# Zynq_DDR_Interface_Termination.net
KiCad netlist of a schematic drawn in Altium Designer
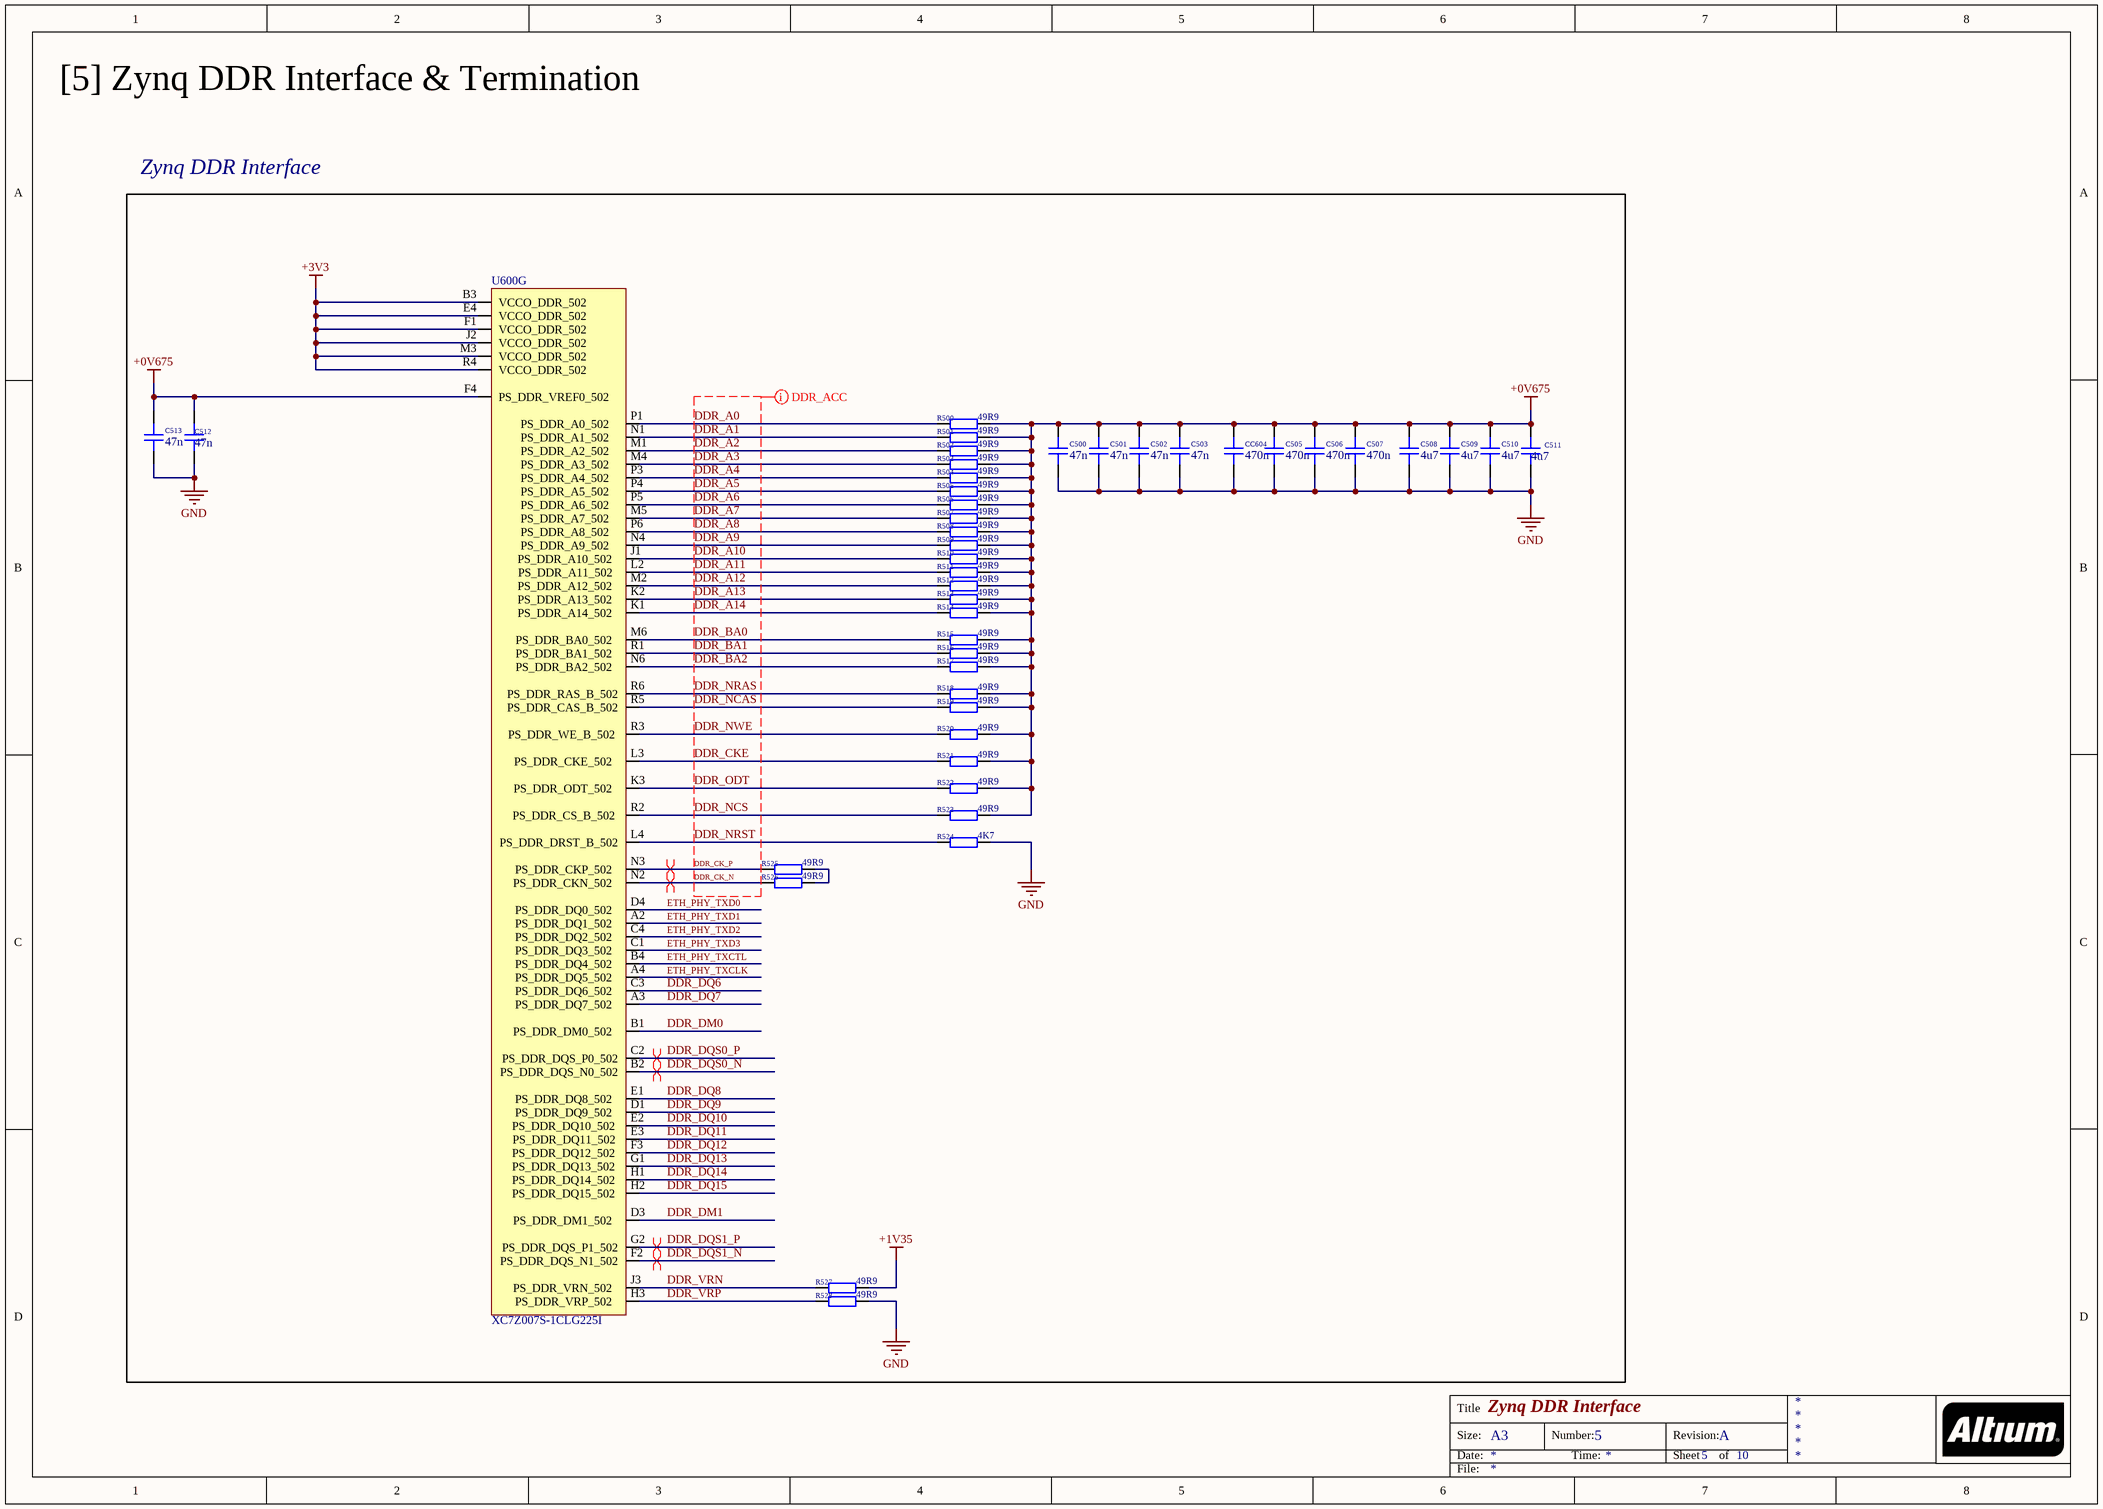
[diagram p0: Zynq DDR Interface & Termination.SchDoc]

(export (version "E")
  (design (tool "Eeschema 10.0.6"))
  (components
    (comp (ref "C500")
      (value "47n")
      (footprint "CAP_1210")
      (description "Capacitor SMD 1210")
      (libsource (lib "Schematic-Lib-PhilsLab") (part "CAP_1210"))
    )
    (comp (ref "C501")
      (value "47n")
      (footprint "CAP_1210")
      (description "Capacitor SMD 1210")
      (libsource (lib "Schematic-Lib-PhilsLab") (part "CAP_1210"))
    )
    (comp (ref "C502")
      (value "47n")
      (footprint "CAP_1210")
      (description "Capacitor SMD 1210")
      (libsource (lib "Schematic-Lib-PhilsLab") (part "CAP_1210"))
    )
    (comp (ref "C503")
      (value "47n")
      (footprint "CAP_1210")
      (description "Capacitor SMD 1210")
      (libsource (lib "Schematic-Lib-PhilsLab") (part "CAP_1210"))
    )
    (comp (ref "C505")
      (value "470n")
      (footprint "CAP_1210")
      (description "Capacitor SMD 1210")
      (libsource (lib "Schematic-Lib-PhilsLab") (part "CAP_1210"))
    )
    (comp (ref "C506")
      (value "470n")
      (footprint "CAP_1210")
      (description "Capacitor SMD 1210")
      (libsource (lib "Schematic-Lib-PhilsLab") (part "CAP_1210"))
    )
    (comp (ref "C507")
      (value "470n")
      (footprint "CAP_1210")
      (description "Capacitor SMD 1210")
      (libsource (lib "Schematic-Lib-PhilsLab") (part "CAP_1210"))
    )
    (comp (ref "C508")
      (value "4u7")
      (footprint "CAP_1210")
      (description "Capacitor SMD 1210")
      (libsource (lib "Schematic-Lib-PhilsLab") (part "CAP_1210"))
    )
    (comp (ref "C509")
      (value "4u7")
      (footprint "CAP_1210")
      (description "Capacitor SMD 1210")
      (libsource (lib "Schematic-Lib-PhilsLab") (part "CAP_1210"))
    )
    (comp (ref "C510")
      (value "4u7")
      (footprint "CAP_1210")
      (description "Capacitor SMD 1210")
      (libsource (lib "Schematic-Lib-PhilsLab") (part "CAP_1210"))
    )
    (comp (ref "C511")
      (value "4u7")
      (footprint "CAP_1210")
      (description "Capacitor SMD 1210")
      (libsource (lib "Schematic-Lib-PhilsLab") (part "CAP_1210"))
    )
    (comp (ref "C512")
      (value "47n")
      (footprint "CAP_1210")
      (description "Capacitor SMD 1210")
      (libsource (lib "Schematic-Lib-PhilsLab") (part "CAP_1210"))
    )
    (comp (ref "C513")
      (value "47n")
      (footprint "CAP_1210")
      (description "Capacitor SMD 1210")
      (libsource (lib "Schematic-Lib-PhilsLab") (part "CAP_1210"))
    )
    (comp (ref "CC604")
      (value "470n")
      (footprint "CAP_1210")
      (description "Capacitor SMD 1210")
      (libsource (lib "Schematic-Lib-PhilsLab") (part "CAP_1210"))
    )
    (comp (ref "R500")
      (value "49R9")
      (footprint "RES_0402")
      (description "Resistor SMD 0402")
      (libsource (lib "Schematic-Lib-PhilsLab") (part "RES_0402"))
    )
    (comp (ref "R501")
      (value "49R9")
      (footprint "RES_0402")
      (description "Resistor SMD 0402")
      (libsource (lib "Schematic-Lib-PhilsLab") (part "RES_0402"))
    )
    (comp (ref "R502")
      (value "49R9")
      (footprint "RES_0402")
      (description "Resistor SMD 0402")
      (libsource (lib "Schematic-Lib-PhilsLab") (part "RES_0402"))
    )
    (comp (ref "R503")
      (value "49R9")
      (footprint "RES_0402")
      (description "Resistor SMD 0402")
      (libsource (lib "Schematic-Lib-PhilsLab") (part "RES_0402"))
    )
    (comp (ref "R504")
      (value "49R9")
      (footprint "RES_0402")
      (description "Resistor SMD 0402")
      (libsource (lib "Schematic-Lib-PhilsLab") (part "RES_0402"))
    )
    (comp (ref "R505")
      (value "49R9")
      (footprint "RES_0402")
      (description "Resistor SMD 0402")
      (libsource (lib "Schematic-Lib-PhilsLab") (part "RES_0402"))
    )
    (comp (ref "R506")
      (value "49R9")
      (footprint "RES_0402")
      (description "Resistor SMD 0402")
      (libsource (lib "Schematic-Lib-PhilsLab") (part "RES_0402"))
    )
    (comp (ref "R507")
      (value "49R9")
      (footprint "RES_0402")
      (description "Resistor SMD 0402")
      (libsource (lib "Schematic-Lib-PhilsLab") (part "RES_0402"))
    )
    (comp (ref "R508")
      (value "49R9")
      (footprint "RES_0402")
      (description "Resistor SMD 0402")
      (libsource (lib "Schematic-Lib-PhilsLab") (part "RES_0402"))
    )
    (comp (ref "R509")
      (value "49R9")
      (footprint "RES_0402")
      (description "Resistor SMD 0402")
      (libsource (lib "Schematic-Lib-PhilsLab") (part "RES_0402"))
    )
    (comp (ref "R510")
      (value "49R9")
      (footprint "RES_0402")
      (description "Resistor SMD 0402")
      (libsource (lib "Schematic-Lib-PhilsLab") (part "RES_0402"))
    )
    (comp (ref "R511")
      (value "49R9")
      (footprint "RES_0402")
      (description "Resistor SMD 0402")
      (libsource (lib "Schematic-Lib-PhilsLab") (part "RES_0402"))
    )
    (comp (ref "R512")
      (value "49R9")
      (footprint "RES_0402")
      (description "Resistor SMD 0402")
      (libsource (lib "Schematic-Lib-PhilsLab") (part "RES_0402"))
    )
    (comp (ref "R513")
      (value "49R9")
      (footprint "RES_0402")
      (description "Resistor SMD 0402")
      (libsource (lib "Schematic-Lib-PhilsLab") (part "RES_0402"))
    )
    (comp (ref "R514")
      (value "49R9")
      (footprint "RES_0402")
      (description "Resistor SMD 0402")
      (libsource (lib "Schematic-Lib-PhilsLab") (part "RES_0402"))
    )
    (comp (ref "R515")
      (value "49R9")
      (footprint "RES_0402")
      (description "Resistor SMD 0402")
      (libsource (lib "Schematic-Lib-PhilsLab") (part "RES_0402"))
    )
    (comp (ref "R516")
      (value "49R9")
      (footprint "RES_0402")
      (description "Resistor SMD 0402")
      (libsource (lib "Schematic-Lib-PhilsLab") (part "RES_0402"))
    )
    (comp (ref "R517")
      (value "49R9")
      (footprint "RES_0402")
      (description "Resistor SMD 0402")
      (libsource (lib "Schematic-Lib-PhilsLab") (part "RES_0402"))
    )
    (comp (ref "R518")
      (value "49R9")
      (footprint "RES_0402")
      (description "Resistor SMD 0402")
      (libsource (lib "Schematic-Lib-PhilsLab") (part "RES_0402"))
    )
    (comp (ref "R519")
      (value "49R9")
      (footprint "RES_0402")
      (description "Resistor SMD 0402")
      (libsource (lib "Schematic-Lib-PhilsLab") (part "RES_0402"))
    )
    (comp (ref "R520")
      (value "49R9")
      (footprint "RES_0402")
      (description "Resistor SMD 0402")
      (libsource (lib "Schematic-Lib-PhilsLab") (part "RES_0402"))
    )
    (comp (ref "R521")
      (value "49R9")
      (footprint "RES_0402")
      (description "Resistor SMD 0402")
      (libsource (lib "Schematic-Lib-PhilsLab") (part "RES_0402"))
    )
    (comp (ref "R522")
      (value "49R9")
      (footprint "RES_0402")
      (description "Resistor SMD 0402")
      (libsource (lib "Schematic-Lib-PhilsLab") (part "RES_0402"))
    )
    (comp (ref "R523")
      (value "49R9")
      (footprint "RES_0402")
      (description "Resistor SMD 0402")
      (libsource (lib "Schematic-Lib-PhilsLab") (part "RES_0402"))
    )
    (comp (ref "R524")
      (value "4K7")
      (footprint "RES_0402")
      (description "Resistor SMD 0402")
      (libsource (lib "Schematic-Lib-PhilsLab") (part "RES_0402"))
    )
    (comp (ref "R525")
      (value "49R9")
      (footprint "RES_0402")
      (description "Resistor SMD 0402")
      (libsource (lib "Schematic-Lib-PhilsLab") (part "RES_0402"))
    )
    (comp (ref "R526")
      (value "49R9")
      (footprint "RES_0402")
      (description "Resistor SMD 0402")
      (libsource (lib "Schematic-Lib-PhilsLab") (part "RES_0402"))
    )
    (comp (ref "R527")
      (value "49R9")
      (footprint "RES_0402")
      (description "Resistor SMD 0402")
      (libsource (lib "Schematic-Lib-PhilsLab") (part "RES_0402"))
    )
    (comp (ref "R528")
      (value "49R9")
      (footprint "RES_0402")
      (description "Resistor SMD 0402")
      (libsource (lib "Schematic-Lib-PhilsLab") (part "RES_0402"))
    )
    (comp (ref "U600")
      (value "XC7Z007S-1CLG225I")
      (footprint "CLG225")
      (description "Xilinx FPGA SoC Zynq 7-Series XC7Z007S CLG255 Package Industrial Temperature Grade")
      (fields (field (name "MANUFACTURER") "Xilinx"))
      (libsource (lib "Schematic-Lib-PhilsLab") (part "XC7Z007S-1CLG225I"))
    )
  )
  (nets
    (net (code "1") (name "+0V675") (class "Default")
      (node (ref "C500") (pin "2") (pinfunction "2_2") (pintype "passive"))
      (node (ref "C501") (pin "2") (pinfunction "2_2") (pintype "passive"))
      (node (ref "C502") (pin "2") (pinfunction "2_2") (pintype "passive"))
      (node (ref "C503") (pin "2") (pinfunction "2_2") (pintype "passive"))
      (node (ref "C505") (pin "2") (pinfunction "2_2") (pintype "passive"))
      (node (ref "C506") (pin "2") (pinfunction "2_2") (pintype "passive"))
      (node (ref "C507") (pin "2") (pinfunction "2_2") (pintype "passive"))
      (node (ref "C508") (pin "2") (pinfunction "2_2") (pintype "passive"))
      (node (ref "C509") (pin "2") (pinfunction "2_2") (pintype "passive"))
      (node (ref "C510") (pin "2") (pinfunction "2_2") (pintype "passive"))
      (node (ref "C511") (pin "2") (pinfunction "2_2") (pintype "passive"))
      (node (ref "C512") (pin "2") (pinfunction "2_2") (pintype "passive"))
      (node (ref "C513") (pin "2") (pinfunction "2_2") (pintype "passive"))
      (node (ref "CC604") (pin "2") (pinfunction "2_2") (pintype "passive"))
      (node (ref "R500") (pin "2") (pinfunction "2_2") (pintype "passive"))
      (node (ref "R501") (pin "2") (pinfunction "2_2") (pintype "passive"))
      (node (ref "R502") (pin "2") (pinfunction "2_2") (pintype "passive"))
      (node (ref "R503") (pin "2") (pinfunction "2_2") (pintype "passive"))
      (node (ref "R504") (pin "2") (pinfunction "2_2") (pintype "passive"))
      (node (ref "R505") (pin "2") (pinfunction "2_2") (pintype "passive"))
      (node (ref "R506") (pin "2") (pinfunction "2_2") (pintype "passive"))
      (node (ref "R507") (pin "2") (pinfunction "2_2") (pintype "passive"))
      (node (ref "R508") (pin "2") (pinfunction "2_2") (pintype "passive"))
      (node (ref "R509") (pin "2") (pinfunction "2_2") (pintype "passive"))
      (node (ref "R510") (pin "2") (pinfunction "2_2") (pintype "passive"))
      (node (ref "R511") (pin "2") (pinfunction "2_2") (pintype "passive"))
      (node (ref "R512") (pin "2") (pinfunction "2_2") (pintype "passive"))
      (node (ref "R513") (pin "2") (pinfunction "2_2") (pintype "passive"))
      (node (ref "R514") (pin "2") (pinfunction "2_2") (pintype "passive"))
      (node (ref "R515") (pin "2") (pinfunction "2_2") (pintype "passive"))
      (node (ref "R516") (pin "2") (pinfunction "2_2") (pintype "passive"))
      (node (ref "R517") (pin "2") (pinfunction "2_2") (pintype "passive"))
      (node (ref "R518") (pin "2") (pinfunction "2_2") (pintype "passive"))
      (node (ref "R519") (pin "2") (pinfunction "2_2") (pintype "passive"))
      (node (ref "R520") (pin "2") (pinfunction "2_2") (pintype "passive"))
      (node (ref "R521") (pin "2") (pinfunction "2_2") (pintype "passive"))
      (node (ref "R522") (pin "2") (pinfunction "2_2") (pintype "passive"))
      (node (ref "R523") (pin "2") (pinfunction "2_2") (pintype "passive"))
      (node (ref "U600") (pin "F4") (pinfunction "PS_DDR_VREF0_502_F4") (pintype "passive"))
    )
    (net (code "2") (name "+1V35") (class "Default")
      (node (ref "R527") (pin "2") (pinfunction "2_2") (pintype "passive"))
    )
    (net (code "3") (name "+3V3") (class "Default")
      (node (ref "U600") (pin "B3") (pinfunction "VCCO_DDR_502_B3") (pintype "passive"))
      (node (ref "U600") (pin "E4") (pinfunction "VCCO_DDR_502_E4") (pintype "passive"))
      (node (ref "U600") (pin "F1") (pinfunction "VCCO_DDR_502_F1") (pintype "passive"))
      (node (ref "U600") (pin "J2") (pinfunction "VCCO_DDR_502_J2") (pintype "passive"))
      (node (ref "U600") (pin "M3") (pinfunction "VCCO_DDR_502_M3") (pintype "passive"))
      (node (ref "U600") (pin "R4") (pinfunction "VCCO_DDR_502_R4") (pintype "passive"))
    )
    (net (code "4") (name "/DDR_A0") (class "Default")
      (node (ref "R500") (pin "1") (pinfunction "1_1") (pintype "passive"))
      (node (ref "U600") (pin "P1") (pinfunction "PS_DDR_A0_502_P1") (pintype "passive"))
    )
    (net (code "5") (name "/DDR_A1") (class "Default")
      (node (ref "R501") (pin "1") (pinfunction "1_1") (pintype "passive"))
      (node (ref "U600") (pin "N1") (pinfunction "PS_DDR_A1_502_N1") (pintype "passive"))
    )
    (net (code "6") (name "/DDR_A2") (class "Default")
      (node (ref "R502") (pin "1") (pinfunction "1_1") (pintype "passive"))
      (node (ref "U600") (pin "M1") (pinfunction "PS_DDR_A2_502_M1") (pintype "passive"))
    )
    (net (code "7") (name "/DDR_A3") (class "Default")
      (node (ref "R503") (pin "1") (pinfunction "1_1") (pintype "passive"))
      (node (ref "U600") (pin "M4") (pinfunction "PS_DDR_A3_502_M4") (pintype "passive"))
    )
    (net (code "8") (name "/DDR_A4") (class "Default")
      (node (ref "R504") (pin "1") (pinfunction "1_1") (pintype "passive"))
      (node (ref "U600") (pin "P3") (pinfunction "PS_DDR_A4_502_P3") (pintype "passive"))
    )
    (net (code "9") (name "/DDR_A5") (class "Default")
      (node (ref "R505") (pin "1") (pinfunction "1_1") (pintype "passive"))
      (node (ref "U600") (pin "P4") (pinfunction "PS_DDR_A5_502_P4") (pintype "passive"))
    )
    (net (code "10") (name "/DDR_A6") (class "Default")
      (node (ref "R506") (pin "1") (pinfunction "1_1") (pintype "passive"))
      (node (ref "U600") (pin "P5") (pinfunction "PS_DDR_A6_502_P5") (pintype "passive"))
    )
    (net (code "11") (name "/DDR_A7") (class "Default")
      (node (ref "R507") (pin "1") (pinfunction "1_1") (pintype "passive"))
      (node (ref "U600") (pin "M5") (pinfunction "PS_DDR_A7_502_M5") (pintype "passive"))
    )
    (net (code "12") (name "/DDR_A8") (class "Default")
      (node (ref "R508") (pin "1") (pinfunction "1_1") (pintype "passive"))
      (node (ref "U600") (pin "P6") (pinfunction "PS_DDR_A8_502_P6") (pintype "passive"))
    )
    (net (code "13") (name "/DDR_A9") (class "Default")
      (node (ref "R509") (pin "1") (pinfunction "1_1") (pintype "passive"))
      (node (ref "U600") (pin "N4") (pinfunction "PS_DDR_A9_502_N4") (pintype "passive"))
    )
    (net (code "14") (name "/DDR_A10") (class "Default")
      (node (ref "R510") (pin "1") (pinfunction "1_1") (pintype "passive"))
      (node (ref "U600") (pin "J1") (pinfunction "PS_DDR_A10_502_J1") (pintype "passive"))
    )
    (net (code "15") (name "/DDR_A11") (class "Default")
      (node (ref "R511") (pin "1") (pinfunction "1_1") (pintype "passive"))
      (node (ref "U600") (pin "L2") (pinfunction "PS_DDR_A11_502_L2") (pintype "passive"))
    )
    (net (code "16") (name "/DDR_A12") (class "Default")
      (node (ref "R512") (pin "1") (pinfunction "1_1") (pintype "passive"))
      (node (ref "U600") (pin "M2") (pinfunction "PS_DDR_A12_502_M2") (pintype "passive"))
    )
    (net (code "17") (name "/DDR_A13") (class "Default")
      (node (ref "R513") (pin "1") (pinfunction "1_1") (pintype "passive"))
      (node (ref "U600") (pin "K2") (pinfunction "PS_DDR_A13_502_K2") (pintype "passive"))
    )
    (net (code "18") (name "/DDR_A14") (class "Default")
      (node (ref "R514") (pin "1") (pinfunction "1_1") (pintype "passive"))
      (node (ref "U600") (pin "K1") (pinfunction "PS_DDR_A14_502_K1") (pintype "passive"))
    )
    (net (code "19") (name "/DDR_BA0") (class "Default")
      (node (ref "R515") (pin "1") (pinfunction "1_1") (pintype "passive"))
      (node (ref "U600") (pin "M6") (pinfunction "PS_DDR_BA0_502_M6") (pintype "passive"))
    )
    (net (code "20") (name "/DDR_BA1") (class "Default")
      (node (ref "R516") (pin "1") (pinfunction "1_1") (pintype "passive"))
      (node (ref "U600") (pin "R1") (pinfunction "PS_DDR_BA1_502_R1") (pintype "passive"))
    )
    (net (code "21") (name "/DDR_BA2") (class "Default")
      (node (ref "R517") (pin "1") (pinfunction "1_1") (pintype "passive"))
      (node (ref "U600") (pin "N6") (pinfunction "PS_DDR_BA2_502_N6") (pintype "passive"))
    )
    (net (code "22") (name "/DDR_CKE") (class "Default")
      (node (ref "R521") (pin "1") (pinfunction "1_1") (pintype "passive"))
      (node (ref "U600") (pin "L3") (pinfunction "PS_DDR_CKE_502_L3") (pintype "passive"))
    )
    (net (code "23") (name "/DDR_CK_N") (class "Default")
      (node (ref "R526") (pin "1") (pinfunction "1_1") (pintype "passive"))
      (node (ref "U600") (pin "N2") (pinfunction "PS_DDR_CKN_502_N2") (pintype "passive"))
    )
    (net (code "24") (name "/DDR_CK_P") (class "Default")
      (node (ref "R525") (pin "1") (pinfunction "1_1") (pintype "passive"))
      (node (ref "U600") (pin "N3") (pinfunction "PS_DDR_CKP_502_N3") (pintype "passive"))
    )
    (net (code "25") (name "/DDR_DM0") (class "Default")
      (node (ref "U600") (pin "B1") (pinfunction "PS_DDR_DM0_502_B1") (pintype "passive"))
    )
    (net (code "26") (name "/DDR_DM1") (class "Default")
      (node (ref "U600") (pin "D3") (pinfunction "PS_DDR_DM1_502_D3") (pintype "passive"))
    )
    (net (code "27") (name "/DDR_DQ6") (class "Default")
      (node (ref "U600") (pin "C3") (pinfunction "PS_DDR_DQ6_502_C3") (pintype "passive"))
    )
    (net (code "28") (name "/DDR_DQ7") (class "Default")
      (node (ref "U600") (pin "A3") (pinfunction "PS_DDR_DQ7_502_A3") (pintype "passive"))
    )
    (net (code "29") (name "/DDR_DQ8") (class "Default")
      (node (ref "U600") (pin "E1") (pinfunction "PS_DDR_DQ8_502_E1") (pintype "passive"))
    )
    (net (code "30") (name "/DDR_DQ9") (class "Default")
      (node (ref "U600") (pin "D1") (pinfunction "PS_DDR_DQ9_502_D1") (pintype "passive"))
    )
    (net (code "31") (name "/DDR_DQ10") (class "Default")
      (node (ref "U600") (pin "E2") (pinfunction "PS_DDR_DQ10_502_E2") (pintype "passive"))
    )
    (net (code "32") (name "/DDR_DQ11") (class "Default")
      (node (ref "U600") (pin "E3") (pinfunction "PS_DDR_DQ11_502_E3") (pintype "passive"))
    )
    (net (code "33") (name "/DDR_DQ12") (class "Default")
      (node (ref "U600") (pin "F3") (pinfunction "PS_DDR_DQ12_502_F3") (pintype "passive"))
    )
    (net (code "34") (name "/DDR_DQ13") (class "Default")
      (node (ref "U600") (pin "G1") (pinfunction "PS_DDR_DQ13_502_G1") (pintype "passive"))
    )
    (net (code "35") (name "/DDR_DQ14") (class "Default")
      (node (ref "U600") (pin "H1") (pinfunction "PS_DDR_DQ14_502_H1") (pintype "passive"))
    )
    (net (code "36") (name "/DDR_DQ15") (class "Default")
      (node (ref "U600") (pin "H2") (pinfunction "PS_DDR_DQ15_502_H2") (pintype "passive"))
    )
    (net (code "37") (name "/DDR_DQS0_N") (class "Default")
      (node (ref "U600") (pin "B2") (pinfunction "PS_DDR_DQS_N0_502_B2") (pintype "passive"))
    )
    (net (code "38") (name "/DDR_DQS0_P") (class "Default")
      (node (ref "U600") (pin "C2") (pinfunction "PS_DDR_DQS_P0_502_C2") (pintype "passive"))
    )
    (net (code "39") (name "/DDR_DQS1_N") (class "Default")
      (node (ref "U600") (pin "F2") (pinfunction "PS_DDR_DQS_N1_502_F2") (pintype "passive"))
    )
    (net (code "40") (name "/DDR_DQS1_P") (class "Default")
      (node (ref "U600") (pin "G2") (pinfunction "PS_DDR_DQS_P1_502_G2") (pintype "passive"))
    )
    (net (code "41") (name "/DDR_NCAS") (class "Default")
      (node (ref "R519") (pin "1") (pinfunction "1_1") (pintype "passive"))
      (node (ref "U600") (pin "R5") (pinfunction "PS_DDR_CAS_B_502_R5") (pintype "passive"))
    )
    (net (code "42") (name "/DDR_NCS") (class "Default")
      (node (ref "R523") (pin "1") (pinfunction "1_1") (pintype "passive"))
      (node (ref "U600") (pin "R2") (pinfunction "PS_DDR_CS_B_502_R2") (pintype "passive"))
    )
    (net (code "43") (name "/DDR_NRAS") (class "Default")
      (node (ref "R518") (pin "1") (pinfunction "1_1") (pintype "passive"))
      (node (ref "U600") (pin "R6") (pinfunction "PS_DDR_RAS_B_502_R6") (pintype "passive"))
    )
    (net (code "44") (name "/DDR_NRST") (class "Default")
      (node (ref "R524") (pin "1") (pinfunction "1_1") (pintype "passive"))
      (node (ref "U600") (pin "L4") (pinfunction "PS_DDR_DRST_B_502_L4") (pintype "passive"))
    )
    (net (code "45") (name "/DDR_NWE") (class "Default")
      (node (ref "R520") (pin "1") (pinfunction "1_1") (pintype "passive"))
      (node (ref "U600") (pin "R3") (pinfunction "PS_DDR_WE_B_502_R3") (pintype "passive"))
    )
    (net (code "46") (name "/DDR_ODT") (class "Default")
      (node (ref "R522") (pin "1") (pinfunction "1_1") (pintype "passive"))
      (node (ref "U600") (pin "K3") (pinfunction "PS_DDR_ODT_502_K3") (pintype "passive"))
    )
    (net (code "47") (name "/DDR_VRN") (class "Default")
      (node (ref "R527") (pin "1") (pinfunction "1_1") (pintype "passive"))
      (node (ref "U600") (pin "J3") (pinfunction "PS_DDR_VRN_502_J3") (pintype "passive"))
    )
    (net (code "48") (name "/DDR_VRP") (class "Default")
      (node (ref "R528") (pin "1") (pinfunction "1_1") (pintype "passive"))
      (node (ref "U600") (pin "H3") (pinfunction "PS_DDR_VRP_502_H3") (pintype "passive"))
    )
    (net (code "49") (name "/ETH_PHY_TXCLK") (class "Default")
      (node (ref "U600") (pin "A4") (pinfunction "PS_DDR_DQ5_502_A4") (pintype "passive"))
    )
    (net (code "50") (name "/ETH_PHY_TXCTL") (class "Default")
      (node (ref "U600") (pin "B4") (pinfunction "PS_DDR_DQ4_502_B4") (pintype "passive"))
    )
    (net (code "51") (name "/ETH_PHY_TXD0") (class "Default")
      (node (ref "U600") (pin "D4") (pinfunction "PS_DDR_DQ0_502_D4") (pintype "passive"))
    )
    (net (code "52") (name "/ETH_PHY_TXD1") (class "Default")
      (node (ref "U600") (pin "A2") (pinfunction "PS_DDR_DQ1_502_A2") (pintype "passive"))
    )
    (net (code "53") (name "/ETH_PHY_TXD2") (class "Default")
      (node (ref "U600") (pin "C4") (pinfunction "PS_DDR_DQ2_502_C4") (pintype "passive"))
    )
    (net (code "54") (name "/ETH_PHY_TXD3") (class "Default")
      (node (ref "U600") (pin "C1") (pinfunction "PS_DDR_DQ3_502_C1") (pintype "passive"))
    )
    (net (code "55") (name "GND") (class "Default")
      (node (ref "C500") (pin "1") (pinfunction "1_1") (pintype "passive"))
      (node (ref "C501") (pin "1") (pinfunction "1_1") (pintype "passive"))
      (node (ref "C502") (pin "1") (pinfunction "1_1") (pintype "passive"))
      (node (ref "C503") (pin "1") (pinfunction "1_1") (pintype "passive"))
      (node (ref "C505") (pin "1") (pinfunction "1_1") (pintype "passive"))
      (node (ref "C506") (pin "1") (pinfunction "1_1") (pintype "passive"))
      (node (ref "C507") (pin "1") (pinfunction "1_1") (pintype "passive"))
      (node (ref "C508") (pin "1") (pinfunction "1_1") (pintype "passive"))
      (node (ref "C509") (pin "1") (pinfunction "1_1") (pintype "passive"))
      (node (ref "C510") (pin "1") (pinfunction "1_1") (pintype "passive"))
      (node (ref "C511") (pin "1") (pinfunction "1_1") (pintype "passive"))
      (node (ref "C512") (pin "1") (pinfunction "1_1") (pintype "passive"))
      (node (ref "C513") (pin "1") (pinfunction "1_1") (pintype "passive"))
      (node (ref "CC604") (pin "1") (pinfunction "1_1") (pintype "passive"))
      (node (ref "R524") (pin "2") (pinfunction "2_2") (pintype "passive"))
      (node (ref "R528") (pin "2") (pinfunction "2_2") (pintype "passive"))
    )
    (net (code "56") (name "Net-(R525-Pad2)") (class "Default")
      (node (ref "R525") (pin "2") (pinfunction "2_2") (pintype "passive"))
      (node (ref "R526") (pin "2") (pinfunction "2_2") (pintype "passive"))
    )
  )
)
